# Load_Bank_Switch_New_Schematic.net
KiCad netlist of a schematic drawn in Altium Designer
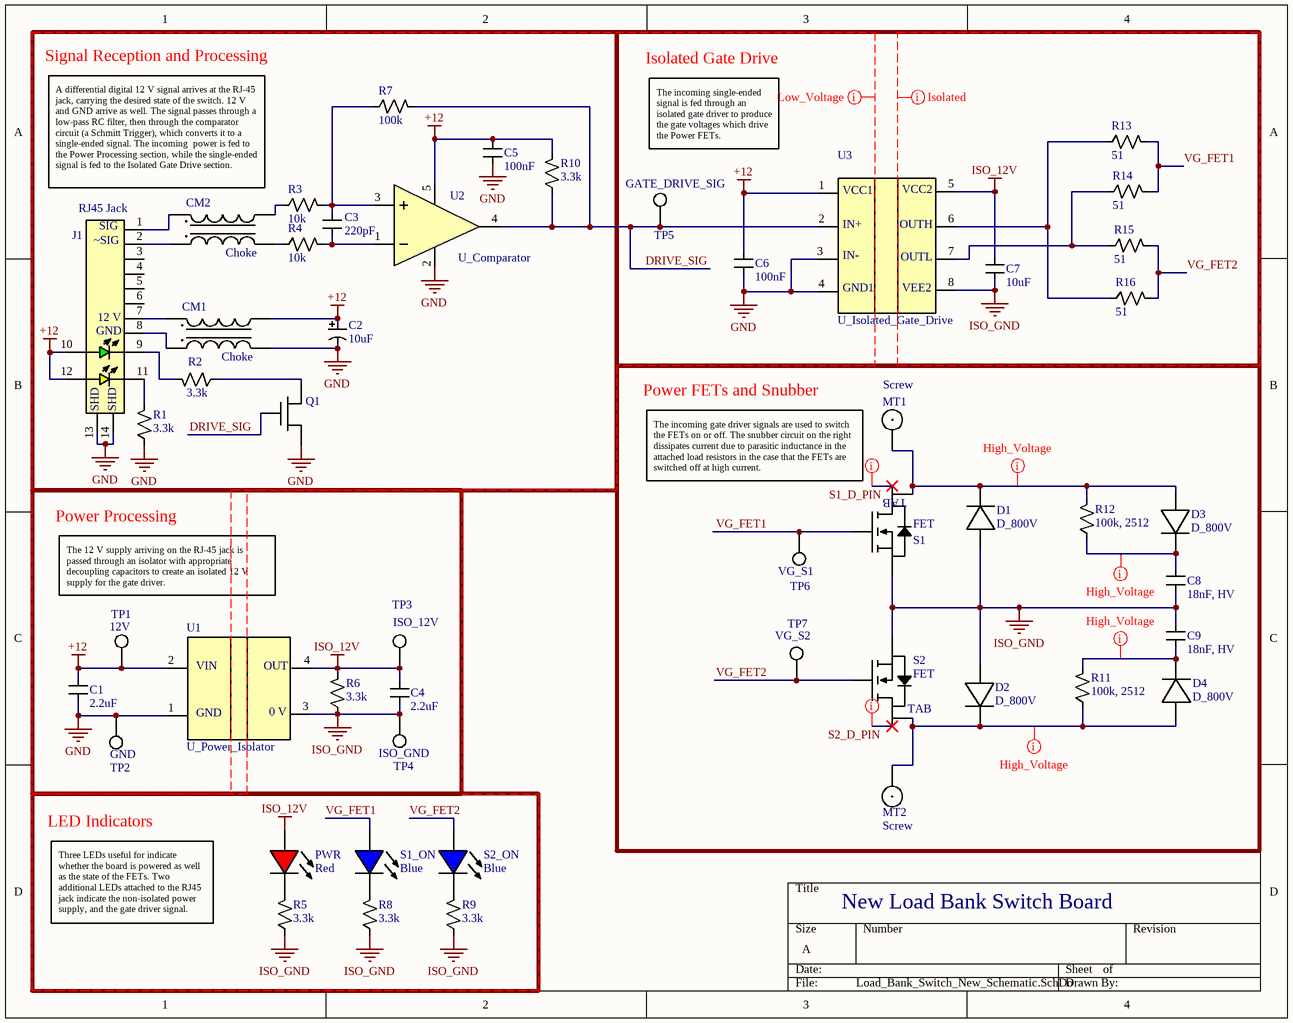
[diagram p0: Load_Bank_Switch_New_Schematic.SchDoc]

(export (version "E")
  (design (tool "Eeschema 10.0.6"))
  (components
    (comp (ref "12V")
      (value "TP1")
      (footprint "0603_TP")
      (description "Test Point 0603")
      (libsource (lib "Load_Bank_New_IntLib") (part "TP_TestPoint"))
    )
    (comp (ref "C1")
      (value "2.2uF")
      (footprint "0603_CAP")
      (description "Capacitor SMD MLCC 2.2 uF 0603")
      (libsource (lib "Load_Bank_New_IntLib") (part "C_2.2uF_0603"))
    )
    (comp (ref "C2")
      (value "10uF")
      (footprint "ALUM_CAP")
      (description "Capacitor SMD Aluminum Electrolytic 10 uF")
      (libsource (lib "Load_Bank_New_IntLib") (part "C_10uF_AlElec"))
    )
    (comp (ref "C3")
      (value "220pF")
      (footprint "0603_CAP")
      (description "Capacitor SMD MLCC 220 pF 0603 5%")
      (libsource (lib "Load_Bank_New_IntLib") (part "C_220pF_0603"))
    )
    (comp (ref "C4")
      (value "2.2uF")
      (footprint "0603_CAP")
      (description "Capacitor SMD MLCC 2.2 uF 0603")
      (libsource (lib "Load_Bank_New_IntLib") (part "C_2.2uF_0603"))
    )
    (comp (ref "C5")
      (value "100nF")
      (footprint "0603_CAP")
      (description "Capacitor SMD MLCC 100 nF 0603")
      (libsource (lib "Load_Bank_New_IntLib") (part "C_100nF_0603"))
    )
    (comp (ref "C6")
      (value "100nF")
      (footprint "0603_CAP")
      (description "Capacitor SMD MLCC 100 nF 0603")
      (libsource (lib "Load_Bank_New_IntLib") (part "C_100nF_0603"))
    )
    (comp (ref "C7")
      (value "10uF")
      (footprint "0805_CAP")
      (description "Capacitor SMD MLCC 10 uF 0805")
      (libsource (lib "Load_Bank_New_IntLib") (part "C_10uF_0805"))
    )
    (comp (ref "C8")
      (value "18nF, HV")
      (footprint "1210_CAP")
      (description "Capacitor SMD MLCC C0G 18 nF 1 kV 1210")
      (libsource (lib "Load_Bank_New_IntLib") (part "C_18nF_1210_1kV"))
    )
    (comp (ref "C9")
      (value "18nF, HV")
      (footprint "1210_CAP")
      (description "Capacitor SMD MLCC C0G 18 nF 1 kV 1210")
      (libsource (lib "Load_Bank_New_IntLib") (part "C_18nF_1210_1kV"))
    )
    (comp (ref "CM1")
      (value "Choke")
      (footprint "CHOKE")
      (description "Common Mode Choke")
      (libsource (lib "Load_Bank_New_IntLib") (part "CM_Common_Mode_Choke"))
    )
    (comp (ref "CM2")
      (value "Choke")
      (footprint "CHOKE")
      (description "Common Mode Choke")
      (libsource (lib "Load_Bank_New_IntLib") (part "CM_Common_Mode_Choke"))
    )
    (comp (ref "D1")
      (value "D_800V")
      (footprint "DIODE")
      (description "Diode 800 V 8 A diode")
      (libsource (lib "Load_Bank_New_IntLib") (part "D_800V"))
    )
    (comp (ref "D2")
      (value "D_800V")
      (footprint "DIODE")
      (description "Diode 800 V 8 A diode")
      (libsource (lib "Load_Bank_New_IntLib") (part "D_800V"))
    )
    (comp (ref "D3")
      (value "D_800V")
      (footprint "DIODE")
      (description "Diode 800 V 8 A diode")
      (libsource (lib "Load_Bank_New_IntLib") (part "D_800V"))
    )
    (comp (ref "D4")
      (value "D_800V")
      (footprint "DIODE")
      (description "Diode 800 V 8 A diode")
      (libsource (lib "Load_Bank_New_IntLib") (part "D_800V"))
    )
    (comp (ref "GATE_DRIVE_SIG")
      (value "TP5")
      (footprint "0603_TP")
      (description "Test Point 0603")
      (libsource (lib "Load_Bank_New_IntLib") (part "TP_TestPoint"))
    )
    (comp (ref "GND")
      (value "TP2")
      (footprint "0603_TP")
      (description "Test Point 0603")
      (libsource (lib "Load_Bank_New_IntLib") (part "TP_TestPoint"))
    )
    (comp (ref "ISO_12V")
      (value "TP3")
      (footprint "0603_TP")
      (description "Test Point 0603")
      (libsource (lib "Load_Bank_New_IntLib") (part "TP_TestPoint"))
    )
    (comp (ref "ISO_GND")
      (value "TP4")
      (footprint "0603_TP")
      (description "Test Point 0603")
      (libsource (lib "Load_Bank_New_IntLib") (part "TP_TestPoint"))
    )
    (comp (ref "J1")
      (value "RJ45 Jack")
      (footprint "RJ45_JACK")
      (description "Jack RJ-45 8-pin")
      (libsource (lib "Load_Bank_New_IntLib") (part "J_RJ45_Jack"))
    )
    (comp (ref "MT1")
      (value "Screw")
      (footprint "MOUNT")
      (description "Screw Mount for connecting board to resistors")
      (libsource (lib "Load_Bank_New_IntLib") (part "MT_Screw"))
    )
    (comp (ref "MT2")
      (value "Screw")
      (footprint "MOUNT")
      (description "Screw Mount for connecting board to resistors")
      (libsource (lib "Load_Bank_New_IntLib") (part "MT_Screw"))
    )
    (comp (ref "PWR")
      (value "Red")
      (footprint "0603_LED")
      (description "LED SMD 0603 Red")
      (libsource (lib "Load_Bank_New_IntLib") (part "LED_0603_Red"))
    )
    (comp (ref "Q1")
      (value "Logic FET")
      (footprint "SOT23")
      (description "N-Channel Logic FET SOT23-3")
      (libsource (lib "Load_Bank_New_IntLib") (part "Q_NFET"))
    )
    (comp (ref "R1")
      (value "3.3k")
      (footprint "0603_RES")
      (description "Resistor 3.3 kOhm 0603 1%")
      (libsource (lib "Load_Bank_New_IntLib") (part "R_3300Ohm_0603_1%"))
    )
    (comp (ref "R2")
      (value "3.3k")
      (footprint "0603_RES")
      (description "Resistor 3.3 kOhm 0603 1%")
      (libsource (lib "Load_Bank_New_IntLib") (part "R_3300Ohm_0603_1%"))
    )
    (comp (ref "R3")
      (value "10k")
      (footprint "0603_RES")
      (description "Resistor 10 kOhm 0603 1%")
      (libsource (lib "Load_Bank_New_IntLib") (part "R_10kOhm_0603_1%"))
    )
    (comp (ref "R4")
      (value "10k")
      (footprint "0603_RES")
      (description "Resistor 10 kOhm 0603 1%")
      (libsource (lib "Load_Bank_New_IntLib") (part "R_10kOhm_0603_1%"))
    )
    (comp (ref "R5")
      (value "3.3k")
      (footprint "0603_RES")
      (description "Resistor 3.3 kOhm 0603 1%")
      (libsource (lib "Load_Bank_New_IntLib") (part "R_3300Ohm_0603_1%"))
    )
    (comp (ref "R6")
      (value "3.3k")
      (footprint "0603_RES")
      (description "Resistor 3.3 kOhm 0603 1%")
      (libsource (lib "Load_Bank_New_IntLib") (part "R_3300Ohm_0603_1%"))
    )
    (comp (ref "R7")
      (value "100k")
      (footprint "0603_RES")
      (description "Resistor 100 kOhm 0603 5%")
      (libsource (lib "Load_Bank_New_IntLib") (part "R_100kOhm_0603_5%"))
    )
    (comp (ref "R8")
      (value "3.3k")
      (footprint "0603_RES")
      (description "Resistor 3.3 kOhm 0603 1%")
      (libsource (lib "Load_Bank_New_IntLib") (part "R_3300Ohm_0603_1%"))
    )
    (comp (ref "R9")
      (value "3.3k")
      (footprint "0603_RES")
      (description "Resistor 3.3 kOhm 0603 1%")
      (libsource (lib "Load_Bank_New_IntLib") (part "R_3300Ohm_0603_1%"))
    )
    (comp (ref "R10")
      (value "3.3k")
      (footprint "0603_RES")
      (description "Resistor 3.3 kOhm 0603 1%")
      (libsource (lib "Load_Bank_New_IntLib") (part "R_3300Ohm_0603_1%"))
    )
    (comp (ref "R11")
      (value "100k, 2512")
      (footprint "2512_RES")
      (description "Resistor 100 kOhm 2512 5%")
      (libsource (lib "Load_Bank_New_IntLib") (part "R_100kOhm_2512_5%"))
    )
    (comp (ref "R12")
      (value "100k, 2512")
      (footprint "2512_RES")
      (description "Resistor 100 kOhm 2512 5%")
      (libsource (lib "Load_Bank_New_IntLib") (part "R_100kOhm_2512_5%"))
    )
    (comp (ref "R13")
      (value "51")
      (footprint "0603_RES")
      (description "Resistor 51 Ohm 0603 1%")
      (libsource (lib "Load_Bank_New_IntLib") (part "R_51Ohm_0603_1%"))
    )
    (comp (ref "R14")
      (value "51")
      (footprint "0603_RES")
      (description "Resistor 51 Ohm 0603 1%")
      (libsource (lib "Load_Bank_New_IntLib") (part "R_51Ohm_0603_1%"))
    )
    (comp (ref "R15")
      (value "51")
      (footprint "0603_RES")
      (description "Resistor 51 Ohm 0603 1%")
      (libsource (lib "Load_Bank_New_IntLib") (part "R_51Ohm_0603_1%"))
    )
    (comp (ref "R16")
      (value "51")
      (footprint "0603_RES")
      (description "Resistor 51 Ohm 0603 1%")
      (libsource (lib "Load_Bank_New_IntLib") (part "R_51Ohm_0603_1%"))
    )
    (comp (ref "S1")
      (value "FET")
      (footprint "FET")
      (description "N-Channel Power FET 650 V 24 A")
      (libsource (lib "Load_Bank_New_IntLib") (part "S_PowerFET"))
    )
    (comp (ref "S1_ON")
      (value "Blue")
      (footprint "0603_LED")
      (description "LED SMD 0603 Blue")
      (libsource (lib "Load_Bank_New_IntLib") (part "LED_0603_Blue"))
    )
    (comp (ref "S2")
      (value "FET")
      (footprint "FET")
      (description "N-Channel Power FET 650 V 24 A")
      (libsource (lib "Load_Bank_New_IntLib") (part "S_PowerFET"))
    )
    (comp (ref "S2_ON")
      (value "Blue")
      (footprint "0603_LED")
      (description "LED SMD 0603 Blue")
      (libsource (lib "Load_Bank_New_IntLib") (part "LED_0603_Blue"))
    )
    (comp (ref "U1")
      (value "U_Power_Isolator")
      (footprint "PWR_ISOLATOR")
      (description "IC Power Isolator 12V-12V DC-DC Converter")
      (libsource (lib "Load_Bank_New_IntLib") (part "U_Power_Isolator"))
    )
    (comp (ref "U2")
      (value "U_Comparator")
      (footprint "COMPARATOR")
      (description "IC Comparator 36 V 300 ns Response Open-Collector")
      (libsource (lib "Load_Bank_New_IntLib") (part "U_Comparator"))
    )
    (comp (ref "U3")
      (value "U_Isolated_Gate_Drive")
      (footprint "GATE_DRIVER")
      (description "IC Isolated Gate Drive 3-15 V Output Supply Split Output")
      (libsource (lib "Load_Bank_New_IntLib") (part "U_Isolated_Gate_Drive"))
    )
    (comp (ref "VG_S1")
      (value "TP6")
      (footprint "0603_TP")
      (description "Test Point 0603")
      (libsource (lib "Load_Bank_New_IntLib") (part "TP_TestPoint"))
    )
    (comp (ref "VG_S2")
      (value "TP7")
      (footprint "0603_TP")
      (description "Test Point 0603")
      (libsource (lib "Load_Bank_New_IntLib") (part "TP_TestPoint"))
    )
  )
  (nets
    (net (code "1") (name "+12") (class "Default")
      (node (ref "12V") (pin "1") (pinfunction "Sig_1") (pintype "passive"))
      (node (ref "C1") (pin "2") (pintype "passive"))
      (node (ref "C2") (pin "2") (pintype "passive"))
      (node (ref "C5") (pin "2") (pintype "passive"))
      (node (ref "C6") (pin "2") (pintype "passive"))
      (node (ref "CM1") (pin "2") (pinfunction "Out1_2") (pintype "passive"))
      (node (ref "J1") (pin "10") (pintype "passive"))
      (node (ref "J1") (pin "12") (pintype "passive"))
      (node (ref "R10") (pin "2") (pintype "passive"))
      (node (ref "U1") (pin "2") (pinfunction "Vin_2") (pintype "passive"))
      (node (ref "U2") (pin "5") (pinfunction "VDD_5") (pintype "passive"))
      (node (ref "U3") (pin "1") (pinfunction "VCC1_1") (pintype "passive"))
    )
    (net (code "2") (name "/DRIVE_SIG") (class "Default")
      (node (ref "GATE_DRIVE_SIG") (pin "1") (pinfunction "Sig_1") (pintype "passive"))
      (node (ref "Q1") (pin "2") (pinfunction "G_2") (pintype "passive"))
      (node (ref "R10") (pin "1") (pintype "passive"))
      (node (ref "R7") (pin "2") (pintype "passive"))
      (node (ref "U2") (pin "4") (pinfunction "Out_4") (pintype "passive"))
      (node (ref "U3") (pin "2") (pinfunction "IN+_2") (pintype "passive"))
    )
    (net (code "3") (name "/S1_D_PIN") (class "Default")
      (node (ref "S1") (pin "2") (pinfunction "D_2") (pintype "passive+no_connect"))
    )
    (net (code "4") (name "/S2_D_PIN") (class "Default")
      (node (ref "S2") (pin "2") (pinfunction "D_2") (pintype "passive+no_connect"))
    )
    (net (code "5") (name "/VG_FET1") (class "Default")
      (node (ref "R13") (pin "2") (pintype "passive"))
      (node (ref "R14") (pin "2") (pintype "passive"))
      (node (ref "S1") (pin "1") (pinfunction "G_1") (pintype "passive"))
      (node (ref "S1_ON") (pin "2") (pintype "passive"))
      (node (ref "VG_S1") (pin "1") (pinfunction "Sig_1") (pintype "passive"))
    )
    (net (code "6") (name "/VG_FET2") (class "Default")
      (node (ref "R15") (pin "2") (pintype "passive"))
      (node (ref "R16") (pin "2") (pintype "passive"))
      (node (ref "S2") (pin "1") (pinfunction "G_1") (pintype "passive"))
      (node (ref "S2_ON") (pin "2") (pintype "passive"))
      (node (ref "VG_S2") (pin "1") (pinfunction "Sig_1") (pintype "passive"))
    )
    (net (code "7") (name "GND") (class "Default")
      (node (ref "C1") (pin "1") (pintype "passive"))
      (node (ref "C2") (pin "1") (pintype "passive"))
      (node (ref "C5") (pin "1") (pintype "passive"))
      (node (ref "C6") (pin "1") (pintype "passive"))
      (node (ref "CM1") (pin "3") (pinfunction "Out2_3") (pintype "passive"))
      (node (ref "GND") (pin "1") (pinfunction "Sig_1") (pintype "passive"))
      (node (ref "J1") (pin "13") (pinfunction "SHD1_13") (pintype "passive"))
      (node (ref "J1") (pin "14") (pinfunction "SHD2_14") (pintype "passive"))
      (node (ref "Q1") (pin "3") (pinfunction "S_3") (pintype "passive"))
      (node (ref "R1") (pin "1") (pintype "passive"))
      (node (ref "U1") (pin "1") (pinfunction "GND_1") (pintype "passive"))
      (node (ref "U2") (pin "2") (pinfunction "GND_2") (pintype "passive"))
      (node (ref "U3") (pin "3") (pinfunction "IN-_3") (pintype "passive"))
      (node (ref "U3") (pin "4") (pinfunction "GND1_4") (pintype "passive"))
    )
    (net (code "8") (name "ISO_12V") (class "Default")
      (node (ref "C4") (pin "2") (pintype "passive"))
      (node (ref "C7") (pin "2") (pintype "passive"))
      (node (ref "ISO_12V") (pin "1") (pinfunction "Sig_1") (pintype "passive"))
      (node (ref "PWR") (pin "2") (pintype "passive"))
      (node (ref "R6") (pin "2") (pintype "passive"))
      (node (ref "U1") (pin "4") (pinfunction "Out_4") (pintype "passive"))
      (node (ref "U3") (pin "5") (pinfunction "VCC2_5") (pintype "passive"))
    )
    (net (code "9") (name "ISO_GND") (class "Default")
      (node (ref "C4") (pin "1") (pintype "passive"))
      (node (ref "C7") (pin "1") (pintype "passive"))
      (node (ref "C8") (pin "1") (pintype "passive"))
      (node (ref "C9") (pin "2") (pintype "passive"))
      (node (ref "D1") (pin "2") (pintype "passive"))
      (node (ref "D2") (pin "2") (pintype "passive"))
      (node (ref "ISO_GND") (pin "1") (pinfunction "Sig_1") (pintype "passive"))
      (node (ref "R5") (pin "1") (pintype "passive"))
      (node (ref "R6") (pin "1") (pintype "passive"))
      (node (ref "R8") (pin "1") (pintype "passive"))
      (node (ref "R9") (pin "1") (pintype "passive"))
      (node (ref "S1") (pin "3") (pinfunction "S_3") (pintype "passive"))
      (node (ref "S2") (pin "3") (pinfunction "S_3") (pintype "passive"))
      (node (ref "U1") (pin "3") (pinfunction "0V_3") (pintype "passive"))
      (node (ref "U3") (pin "8") (pinfunction "VEE2_8") (pintype "passive"))
    )
    (net (code "10") (name "Net-(C8-Pad2)") (class "Default")
      (node (ref "C8") (pin "2") (pintype "passive"))
      (node (ref "D3") (pin "1") (pintype "passive"))
      (node (ref "R12") (pin "1") (pintype "passive"))
    )
    (net (code "11") (name "Net-(C9-Pad1)") (class "Default")
      (node (ref "C9") (pin "1") (pintype "passive"))
      (node (ref "D4") (pin "1") (pintype "passive"))
      (node (ref "R11") (pin "2") (pintype "passive"))
    )
    (net (code "12") (name "Net-(CM1-In1)") (class "Default")
      (node (ref "CM1") (pin "1") (pinfunction "In1_1") (pintype "passive"))
      (node (ref "J1") (pin "7") (pinfunction "12_V_7") (pintype "passive"))
    )
    (net (code "13") (name "Net-(CM1-In2)") (class "Default")
      (node (ref "CM1") (pin "4") (pinfunction "In2_4") (pintype "passive"))
      (node (ref "J1") (pin "8") (pinfunction "GND_8") (pintype "passive"))
    )
    (net (code "14") (name "Net-(CM2-In1)") (class "Default")
      (node (ref "CM2") (pin "1") (pinfunction "In1_1") (pintype "passive"))
      (node (ref "J1") (pin "1") (pinfunction "Sig1_1") (pintype "passive"))
    )
    (net (code "15") (name "Net-(CM2-In2)") (class "Default")
      (node (ref "CM2") (pin "4") (pinfunction "In2_4") (pintype "passive"))
      (node (ref "J1") (pin "2") (pinfunction "Sig2_2") (pintype "passive"))
    )
    (net (code "16") (name "Net-(CM2-Out1)") (class "Default")
      (node (ref "CM2") (pin "2") (pinfunction "Out1_2") (pintype "passive"))
      (node (ref "R3") (pin "1") (pintype "passive"))
    )
    (net (code "17") (name "Net-(CM2-Out2)") (class "Default")
      (node (ref "CM2") (pin "3") (pinfunction "Out2_3") (pintype "passive"))
      (node (ref "R4") (pin "1") (pintype "passive"))
    )
    (net (code "18") (name "Net-(J1-Pad9)") (class "Default")
      (node (ref "J1") (pin "9") (pintype "passive"))
      (node (ref "R2") (pin "2") (pintype "passive"))
    )
    (net (code "19") (name "Net-(J1-Pad11)") (class "Default")
      (node (ref "J1") (pin "11") (pintype "passive"))
      (node (ref "R1") (pin "2") (pintype "passive"))
    )
    (net (code "20") (name "Net-(PWR-Pad1)") (class "Default")
      (node (ref "PWR") (pin "1") (pintype "passive"))
      (node (ref "R5") (pin "2") (pintype "passive"))
    )
    (net (code "21") (name "Net-(Q1-D)") (class "Default")
      (node (ref "Q1") (pin "1") (pinfunction "D_1") (pintype "passive"))
      (node (ref "R2") (pin "1") (pintype "passive"))
    )
    (net (code "22") (name "Net-(R8-Pad2)") (class "Default")
      (node (ref "R8") (pin "2") (pintype "passive"))
      (node (ref "S1_ON") (pin "1") (pintype "passive"))
    )
    (net (code "23") (name "Net-(R9-Pad2)") (class "Default")
      (node (ref "R9") (pin "2") (pintype "passive"))
      (node (ref "S2_ON") (pin "1") (pintype "passive"))
    )
    (net (code "24") (name "Net-(S1-TAB)") (class "Default")
      (node (ref "D1") (pin "1") (pintype "passive"))
      (node (ref "D3") (pin "2") (pintype "passive"))
      (node (ref "MT1") (pin "1") (pintype "passive"))
      (node (ref "R12") (pin "2") (pintype "passive"))
      (node (ref "S1") (pin "4") (pinfunction "TAB_4") (pintype "passive"))
    )
    (net (code "25") (name "Net-(S2-TAB)") (class "Default")
      (node (ref "D2") (pin "1") (pintype "passive"))
      (node (ref "D4") (pin "2") (pintype "passive"))
      (node (ref "MT2") (pin "1") (pintype "passive"))
      (node (ref "R11") (pin "1") (pintype "passive"))
      (node (ref "S2") (pin "4") (pinfunction "TAB_4") (pintype "passive"))
    )
    (net (code "26") (name "Net-(U2-V+)") (class "Default")
      (node (ref "C3") (pin "2") (pintype "passive"))
      (node (ref "R3") (pin "2") (pintype "passive"))
      (node (ref "R7") (pin "1") (pintype "passive"))
      (node (ref "U2") (pin "3") (pinfunction "V+_3") (pintype "passive"))
    )
    (net (code "27") (name "Net-(U2-V-)") (class "Default")
      (node (ref "C3") (pin "1") (pintype "passive"))
      (node (ref "R4") (pin "2") (pintype "passive"))
      (node (ref "U2") (pin "1") (pinfunction "V-_1") (pintype "passive"))
    )
    (net (code "28") (name "Net-(U3-OUTH)") (class "Default")
      (node (ref "R13") (pin "1") (pintype "passive"))
      (node (ref "R16") (pin "1") (pintype "passive"))
      (node (ref "U3") (pin "6") (pinfunction "OUTH_6") (pintype "passive"))
    )
    (net (code "29") (name "Net-(U3-OUTL)") (class "Default")
      (node (ref "R14") (pin "1") (pintype "passive"))
      (node (ref "R15") (pin "1") (pintype "passive"))
      (node (ref "U3") (pin "7") (pinfunction "OUTL_7") (pintype "passive"))
    )
    (net (code "30") (name "unconnected-(J1-NC-Pad3)") (class "Default")
      (node (ref "J1") (pin "3") (pinfunction "NC_3") (pintype "passive"))
    )
    (net (code "31") (name "unconnected-(J1-NC-Pad4)") (class "Default")
      (node (ref "J1") (pin "4") (pinfunction "NC_4") (pintype "passive"))
    )
    (net (code "32") (name "unconnected-(J1-NC-Pad5)") (class "Default")
      (node (ref "J1") (pin "5") (pinfunction "NC_5") (pintype "passive"))
    )
    (net (code "33") (name "unconnected-(J1-NC-Pad6)") (class "Default")
      (node (ref "J1") (pin "6") (pinfunction "NC_6") (pintype "passive"))
    )
  )
)
